# Opamps.net
KiCad netlist of a schematic drawn in Altium Designer
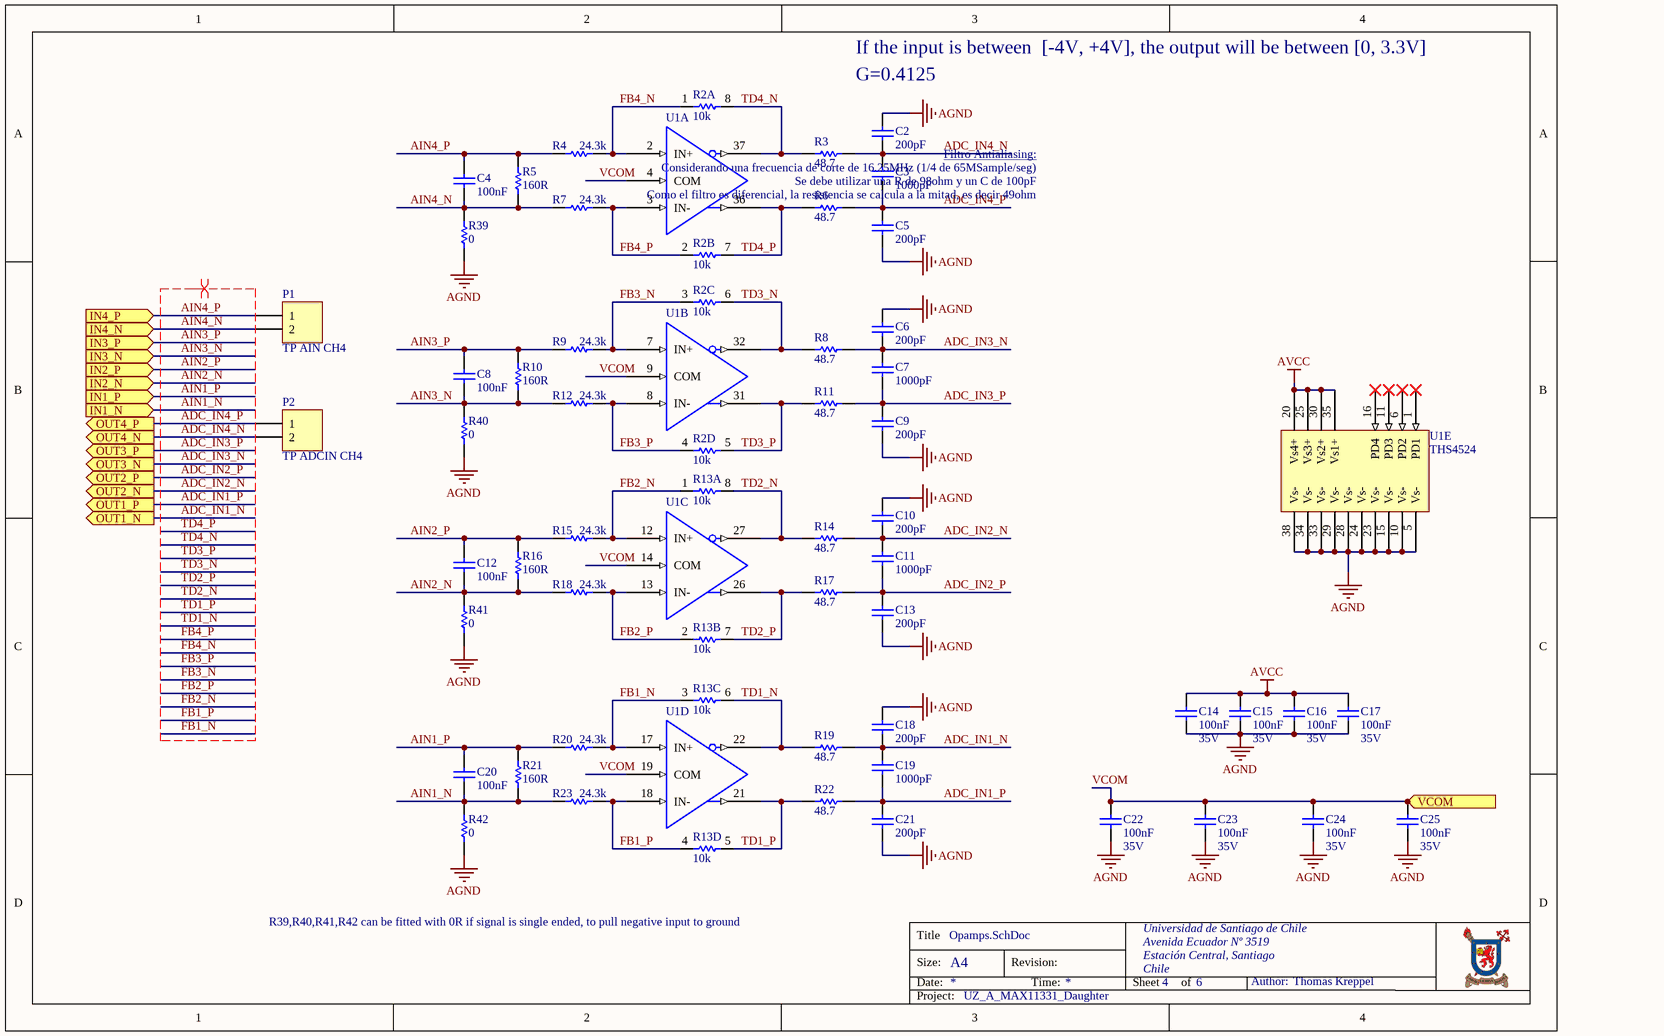
[diagram p0: Opamps.SchDoc]

(export (version "E")
  (design (tool "Eeschema 10.0.6"))
  (components
    (comp (ref "C2")
      (value "200pF")
      (footprint "CAP_0603")
      (description "Capacitor")
      (fields
        (field (name "MPN") "0603N201J500CT")
        (field (name "MF") "Walsin")
        (field (name "PUBLISHER") "Altium Limited")
      )
      (libsource (lib "Componentes_SOC") (part "Cap_0603"))
    )
    (comp (ref "C3")
      (value "1000pF")
      (footprint "CAP_0603")
      (description "Capacitor")
      (fields
        (field (name "MPN") "885012006029")
        (field (name "MF") "Würth Elektronik")
        (field (name "PUBLISHER") "Altium Limited")
      )
      (libsource (lib "Componentes_SOC") (part "Cap_0603"))
    )
    (comp (ref "C4")
      (value "100nF")
      (footprint "RES_1206")
      (description "Capacitor")
      (fields (field (name "MPN") "C1206C104K3RACTU") (field (name "VOLTAGE") "16V"))
      (libsource (lib "Componentes_SOC") (part "Cap_1206"))
    )
    (comp (ref "C5")
      (value "200pF")
      (footprint "CAP_0603")
      (description "Capacitor")
      (fields
        (field (name "MPN") "0603N201J500CT")
        (field (name "MF") "Walsin")
        (field (name "PUBLISHER") "Altium Limited")
      )
      (libsource (lib "Componentes_SOC") (part "Cap_0603"))
    )
    (comp (ref "C6")
      (value "200pF")
      (footprint "CAP_0603")
      (description "Capacitor")
      (fields
        (field (name "MPN") "0603N201J500CT")
        (field (name "MF") "Walsin")
        (field (name "PUBLISHER") "Altium Limited")
      )
      (libsource (lib "Componentes_SOC") (part "Cap_0603"))
    )
    (comp (ref "C7")
      (value "1000pF")
      (footprint "CAP_0603")
      (description "Capacitor")
      (fields
        (field (name "MPN") "885012006029")
        (field (name "MF") "Würth Elektronik")
        (field (name "PUBLISHER") "Altium Limited")
      )
      (libsource (lib "Componentes_SOC") (part "Cap_0603"))
    )
    (comp (ref "C8")
      (value "100nF")
      (footprint "RES_1206")
      (description "Capacitor")
      (fields (field (name "MPN") "C1206C104K3RACTU") (field (name "VOLTAGE") "16V"))
      (libsource (lib "Componentes_SOC") (part "Cap_1206"))
    )
    (comp (ref "C9")
      (value "200pF")
      (footprint "CAP_0603")
      (description "Capacitor")
      (fields
        (field (name "MPN") "0603N201J500CT")
        (field (name "MF") "Walsin")
        (field (name "PUBLISHER") "Altium Limited")
      )
      (libsource (lib "Componentes_SOC") (part "Cap_0603"))
    )
    (comp (ref "C10")
      (value "200pF")
      (footprint "CAP_0603")
      (description "Capacitor")
      (fields
        (field (name "MPN") "0603N201J500CT")
        (field (name "MF") "Walsin")
        (field (name "PUBLISHER") "Altium Limited")
      )
      (libsource (lib "Componentes_SOC") (part "Cap_0603"))
    )
    (comp (ref "C11")
      (value "1000pF")
      (footprint "CAP_0603")
      (description "Capacitor")
      (fields
        (field (name "MPN") "885012006029")
        (field (name "MF") "Würth Elektronik")
        (field (name "PUBLISHER") "Altium Limited")
      )
      (libsource (lib "Componentes_SOC") (part "Cap_0603"))
    )
    (comp (ref "C12")
      (value "100nF")
      (footprint "RES_1206")
      (description "Capacitor")
      (fields (field (name "MPN") "C1206C104K3RACTU") (field (name "VOLTAGE") "16V"))
      (libsource (lib "Componentes_SOC") (part "Cap_1206"))
    )
    (comp (ref "C13")
      (value "200pF")
      (footprint "CAP_0603")
      (description "Capacitor")
      (fields
        (field (name "MPN") "0603N201J500CT")
        (field (name "MF") "Walsin")
        (field (name "PUBLISHER") "Altium Limited")
      )
      (libsource (lib "Componentes_SOC") (part "Cap_0603"))
    )
    (comp (ref "C14")
      (value "100nF")
      (footprint "CAP_0603")
      (description "Capacitor")
      (fields
        (field (name "MPN") "C0603C104M5RACTU")
        (field (name "MF") "KEMET")
        (field (name "VOLTAGE") "35V")
        (field (name "PUBLISHER") "Altium Limited")
      )
      (libsource (lib "Componentes_SOC") (part "Cap_0603"))
    )
    (comp (ref "C15")
      (value "100nF")
      (footprint "CAP_0603")
      (description "Capacitor")
      (fields
        (field (name "MPN") "C0603C104M5RACTU")
        (field (name "MF") "KEMET")
        (field (name "VOLTAGE") "35V")
        (field (name "PUBLISHER") "Altium Limited")
      )
      (libsource (lib "Componentes_SOC") (part "Cap_0603"))
    )
    (comp (ref "C16")
      (value "100nF")
      (footprint "CAP_0603")
      (description "Capacitor")
      (fields
        (field (name "MPN") "C0603C104M5RACTU")
        (field (name "MF") "KEMET")
        (field (name "VOLTAGE") "35V")
        (field (name "PUBLISHER") "Altium Limited")
      )
      (libsource (lib "Componentes_SOC") (part "Cap_0603"))
    )
    (comp (ref "C17")
      (value "100nF")
      (footprint "CAP_0603")
      (description "Capacitor")
      (fields
        (field (name "MPN") "C0603C104M5RACTU")
        (field (name "MF") "KEMET")
        (field (name "VOLTAGE") "35V")
        (field (name "PUBLISHER") "Altium Limited")
      )
      (libsource (lib "Componentes_SOC") (part "Cap_0603"))
    )
    (comp (ref "C18")
      (value "200pF")
      (footprint "CAP_0603")
      (description "Capacitor")
      (fields
        (field (name "MPN") "0603N201J500CT")
        (field (name "MF") "Walsin")
        (field (name "PUBLISHER") "Altium Limited")
      )
      (libsource (lib "Componentes_SOC") (part "Cap_0603"))
    )
    (comp (ref "C19")
      (value "1000pF")
      (footprint "CAP_0603")
      (description "Capacitor")
      (fields
        (field (name "MPN") "885012006029")
        (field (name "MF") "Würth Elektronik")
        (field (name "PUBLISHER") "Altium Limited")
      )
      (libsource (lib "Componentes_SOC") (part "Cap_0603"))
    )
    (comp (ref "C20")
      (value "100nF")
      (footprint "RES_1206")
      (description "Capacitor")
      (fields (field (name "MPN") "C1206C104K3RACTU") (field (name "VOLTAGE") "16V"))
      (libsource (lib "Componentes_SOC") (part "Cap_1206"))
    )
    (comp (ref "C21")
      (value "200pF")
      (footprint "CAP_0603")
      (description "Capacitor")
      (fields
        (field (name "MPN") "0603N201J500CT")
        (field (name "MF") "Walsin")
        (field (name "PUBLISHER") "Altium Limited")
      )
      (libsource (lib "Componentes_SOC") (part "Cap_0603"))
    )
    (comp (ref "C22")
      (value "100nF")
      (footprint "CAP_0603")
      (description "Capacitor")
      (fields
        (field (name "MPN") "C0603C104M5RACTU")
        (field (name "MF") "KEMET")
        (field (name "VOLTAGE") "35V")
        (field (name "PUBLISHER") "Altium Limited")
      )
      (libsource (lib "Componentes_SOC") (part "Cap_0603"))
    )
    (comp (ref "C23")
      (value "100nF")
      (footprint "CAP_0603")
      (description "Capacitor")
      (fields
        (field (name "MPN") "C0603C104M5RACTU")
        (field (name "MF") "KEMET")
        (field (name "VOLTAGE") "35V")
        (field (name "PUBLISHER") "Altium Limited")
      )
      (libsource (lib "Componentes_SOC") (part "Cap_0603"))
    )
    (comp (ref "C24")
      (value "100nF")
      (footprint "CAP_0603")
      (description "Capacitor")
      (fields
        (field (name "MPN") "C0603C104M5RACTU")
        (field (name "MF") "KEMET")
        (field (name "VOLTAGE") "35V")
        (field (name "PUBLISHER") "Altium Limited")
      )
      (libsource (lib "Componentes_SOC") (part "Cap_0603"))
    )
    (comp (ref "C25")
      (value "100nF")
      (footprint "CAP_0603")
      (description "Capacitor")
      (fields
        (field (name "MPN") "C0603C104M5RACTU")
        (field (name "MF") "KEMET")
        (field (name "VOLTAGE") "35V")
        (field (name "PUBLISHER") "Altium Limited")
      )
      (libsource (lib "Componentes_SOC") (part "Cap_0603"))
    )
    (comp (ref "P1")
      (value "TP AIN CH4")
      (footprint "HDR1X2")
      (description "Header, 2-Pin")
      (fields (field (name "PUBLISHER") "Altium Limited"))
      (libsource (lib "Miscellaneous Connectors") (part "Header 2"))
    )
    (comp (ref "P2")
      (value "TP ADCIN CH4")
      (footprint "HDR1X2")
      (description "Header, 2-Pin")
      (fields (field (name "PUBLISHER") "Altium Limited"))
      (libsource (lib "Miscellaneous Connectors") (part "Header 2"))
    )
    (comp (ref "R2")
      (value "10k")
      (footprint "CAC-80P320X160-8N")
      (description "Chip Resistor Array 0606, 4xR")
      (fields
        (field (name "MF") "Vishay")
        (field (name "MPN") "ACASA1002S1002P100")
        (field (name "CREATED") "Kreppel_0420")
      )
      (libsource (lib "Componentes_SOC") (part "ResArray 1206"))
    )
    (comp (ref "R3")
      (value "48.7")
      (footprint "RES_0603")
      (fields
        (field (name "MPN") "ERA-3AEB48R7V")
        (field (name "MF") "Panasonic")
        (field (name "TOLERANCE") "0.1%")
        (field (name "PUBLISHER") "Altium Limited")
      )
      (libsource (lib "Componentes_SOC") (part "Res0603"))
    )
    (comp (ref "R4")
      (value "24.3k")
      (footprint "RES_0603")
      (fields
        (field (name "MPN") "ERJ-PB3B2432V")
        (field (name "MF") "Panasonic")
        (field (name "TOLERANCE") "0.1%")
        (field (name "PUBLISHER") "Altium Limited")
      )
      (libsource (lib "Componentes_SOC") (part "Res0603"))
    )
    (comp (ref "R5")
      (value "160R")
      (footprint "RES_1206")
      (description "Limiter Resistor")
      (fields
        (field (name "MPN") "RT1206BRD07160RL")
        (field (name "MF") "Yageo")
        (field (name "PUBLISHER") "Altium Limited")
      )
      (libsource (lib "Miscellaneous Devices") (part "Res Semi"))
    )
    (comp (ref "R6")
      (value "48.7")
      (footprint "RES_0603")
      (fields
        (field (name "MPN") "ERA-3AEB48R7V")
        (field (name "MF") "Panasonic")
        (field (name "TOLERANCE") "0.1%")
        (field (name "PUBLISHER") "Altium Limited")
      )
      (libsource (lib "Componentes_SOC") (part "Res0603"))
    )
    (comp (ref "R7")
      (value "24.3k")
      (footprint "RES_0603")
      (fields
        (field (name "MPN") "ERJ-PB3B2432V")
        (field (name "MF") "Panasonic")
        (field (name "TOLERANCE") "0.1%")
        (field (name "PUBLISHER") "Altium Limited")
      )
      (libsource (lib "Componentes_SOC") (part "Res0603"))
    )
    (comp (ref "R8")
      (value "48.7")
      (footprint "RES_0603")
      (fields
        (field (name "MPN") "ERA-3AEB48R7V")
        (field (name "MF") "Panasonic")
        (field (name "TOLERANCE") "0.1%")
        (field (name "PUBLISHER") "Altium Limited")
      )
      (libsource (lib "Componentes_SOC") (part "Res0603"))
    )
    (comp (ref "R9")
      (value "24.3k")
      (footprint "RES_0603")
      (fields
        (field (name "MPN") "ERJ-PB3B2432V")
        (field (name "MF") "Panasonic")
        (field (name "TOLERANCE") "0.1%")
        (field (name "PUBLISHER") "Altium Limited")
      )
      (libsource (lib "Componentes_SOC") (part "Res0603"))
    )
    (comp (ref "R10")
      (value "160R")
      (footprint "RES_1206")
      (description "Limiter Resistor")
      (fields
        (field (name "MPN") "RT1206BRD07160RL")
        (field (name "MF") "Yageo")
        (field (name "PUBLISHER") "Altium Limited")
      )
      (libsource (lib "Miscellaneous Devices") (part "Res Semi"))
    )
    (comp (ref "R11")
      (value "48.7")
      (footprint "RES_0603")
      (fields
        (field (name "MPN") "ERA-3AEB48R7V")
        (field (name "MF") "Panasonic")
        (field (name "TOLERANCE") "0.1%")
        (field (name "PUBLISHER") "Altium Limited")
      )
      (libsource (lib "Componentes_SOC") (part "Res0603"))
    )
    (comp (ref "R12")
      (value "24.3k")
      (footprint "RES_0603")
      (fields
        (field (name "MPN") "ERJ-PB3B2432V")
        (field (name "MF") "Panasonic")
        (field (name "TOLERANCE") "0.1%")
        (field (name "PUBLISHER") "Altium Limited")
      )
      (libsource (lib "Componentes_SOC") (part "Res0603"))
    )
    (comp (ref "R13")
      (value "10k")
      (footprint "CAC-80P320X160-8N")
      (description "Chip Resistor Array 0606, 4xR")
      (fields
        (field (name "MF") "Vishay")
        (field (name "MPN") "ACASA1002S1002P100")
        (field (name "CREATED") "Kreppel_0420")
      )
      (libsource (lib "Componentes_SOC") (part "ResArray 1206"))
    )
    (comp (ref "R14")
      (value "48.7")
      (footprint "RES_0603")
      (fields
        (field (name "MPN") "ERA-3AEB48R7V")
        (field (name "MF") "Panasonic")
        (field (name "TOLERANCE") "0.1%")
        (field (name "PUBLISHER") "Altium Limited")
      )
      (libsource (lib "Componentes_SOC") (part "Res0603"))
    )
    (comp (ref "R15")
      (value "24.3k")
      (footprint "RES_0603")
      (fields
        (field (name "MPN") "ERJ-PB3B2432V")
        (field (name "MF") "Panasonic")
        (field (name "TOLERANCE") "0.1%")
        (field (name "PUBLISHER") "Altium Limited")
      )
      (libsource (lib "Componentes_SOC") (part "Res0603"))
    )
    (comp (ref "R16")
      (value "160R")
      (footprint "RES_1206")
      (description "Limiter Resistor")
      (fields
        (field (name "MPN") "RT1206BRD07160RL")
        (field (name "MF") "Yageo")
        (field (name "PUBLISHER") "Altium Limited")
      )
      (libsource (lib "Miscellaneous Devices") (part "Res Semi"))
    )
    (comp (ref "R17")
      (value "48.7")
      (footprint "RES_0603")
      (fields
        (field (name "MPN") "ERA-3AEB48R7V")
        (field (name "MF") "Panasonic")
        (field (name "TOLERANCE") "0.1%")
        (field (name "PUBLISHER") "Altium Limited")
      )
      (libsource (lib "Componentes_SOC") (part "Res0603"))
    )
    (comp (ref "R18")
      (value "24.3k")
      (footprint "RES_0603")
      (fields
        (field (name "MPN") "ERJ-PB3B2432V")
        (field (name "MF") "Panasonic")
        (field (name "TOLERANCE") "0.1%")
        (field (name "PUBLISHER") "Altium Limited")
      )
      (libsource (lib "Componentes_SOC") (part "Res0603"))
    )
    (comp (ref "R19")
      (value "48.7")
      (footprint "RES_0603")
      (fields
        (field (name "MPN") "ERA-3AEB48R7V")
        (field (name "MF") "Panasonic")
        (field (name "TOLERANCE") "0.1%")
        (field (name "PUBLISHER") "Altium Limited")
      )
      (libsource (lib "Componentes_SOC") (part "Res0603"))
    )
    (comp (ref "R20")
      (value "24.3k")
      (footprint "RES_0603")
      (fields
        (field (name "MPN") "ERJ-PB3B2432V")
        (field (name "MF") "Panasonic")
        (field (name "TOLERANCE") "0.1%")
        (field (name "PUBLISHER") "Altium Limited")
      )
      (libsource (lib "Componentes_SOC") (part "Res0603"))
    )
    (comp (ref "R21")
      (value "160R")
      (footprint "RES_1206")
      (description "Limiter Resistor")
      (fields
        (field (name "MPN") "RT1206BRD07160RL")
        (field (name "MF") "Yageo")
        (field (name "PUBLISHER") "Altium Limited")
      )
      (libsource (lib "Miscellaneous Devices") (part "Res Semi"))
    )
    (comp (ref "R22")
      (value "48.7")
      (footprint "RES_0603")
      (fields
        (field (name "MPN") "ERA-3AEB48R7V")
        (field (name "MF") "Panasonic")
        (field (name "TOLERANCE") "0.1%")
        (field (name "PUBLISHER") "Altium Limited")
      )
      (libsource (lib "Componentes_SOC") (part "Res0603"))
    )
    (comp (ref "R23")
      (value "24.3k")
      (footprint "RES_0603")
      (fields
        (field (name "MPN") "ERJ-PB3B2432V")
        (field (name "MF") "Panasonic")
        (field (name "TOLERANCE") "0.1%")
        (field (name "PUBLISHER") "Altium Limited")
      )
      (libsource (lib "Componentes_SOC") (part "Res0603"))
    )
    (comp (ref "R39")
      (value "0")
      (footprint "RES_0603")
      (fields
        (field (name "MPN") "RC0603JR-070RL")
        (field (name "MF") "Yageo")
        (field (name "TOLERANCE") "1%")
        (field (name "PUBLISHER") "Altium Limited")
      )
      (libsource (lib "Componentes_SOC") (part "Res0603"))
    )
    (comp (ref "R40")
      (value "0")
      (footprint "RES_0603")
      (fields
        (field (name "MPN") "RC0603JR-070RL")
        (field (name "MF") "Yageo")
        (field (name "TOLERANCE") "1%")
        (field (name "PUBLISHER") "Altium Limited")
      )
      (libsource (lib "Componentes_SOC") (part "Res0603"))
    )
    (comp (ref "R41")
      (value "0")
      (footprint "RES_0603")
      (fields
        (field (name "MPN") "RC0603JR-070RL")
        (field (name "MF") "Yageo")
        (field (name "TOLERANCE") "1%")
        (field (name "PUBLISHER") "Altium Limited")
      )
      (libsource (lib "Componentes_SOC") (part "Res0603"))
    )
    (comp (ref "R42")
      (value "0")
      (footprint "RES_0603")
      (fields
        (field (name "MPN") "RC0603JR-070RL")
        (field (name "MF") "Yageo")
        (field (name "TOLERANCE") "1%")
        (field (name "PUBLISHER") "Altium Limited")
      )
      (libsource (lib "Componentes_SOC") (part "Res0603"))
    )
    (comp (ref "U1")
      (value "THS4524")
      (footprint "THS4524 Footprint")
      (description "Quad Channel fully differential Amplilfier")
      (fields
        (field (name "MF") "Texas Instruments")
        (field (name "LCSC PART NUMBER") "C2057434")
        (field (name "CREATED") "20190720_Kreppel")
      )
      (libsource (lib "Componentes_SOC") (part "THS4524_1"))
    )
  )
  (nets
    (net (code "1") (name "/ADC_IN1_N") (class "Default")
      (node (ref "C18") (pin "2") (pinfunction "2_2") (pintype "passive"))
      (node (ref "C19") (pin "1") (pinfunction "1_1") (pintype "passive"))
      (node (ref "R19") (pin "1") (pinfunction "1_1") (pintype "passive"))
    )
    (net (code "2") (name "/ADC_IN1_P") (class "Default")
      (node (ref "C19") (pin "2") (pinfunction "2_2") (pintype "passive"))
      (node (ref "C21") (pin "1") (pinfunction "1_1") (pintype "passive"))
      (node (ref "R22") (pin "1") (pinfunction "1_1") (pintype "passive"))
    )
    (net (code "3") (name "/ADC_IN2_N") (class "Default")
      (node (ref "C10") (pin "2") (pinfunction "2_2") (pintype "passive"))
      (node (ref "C11") (pin "1") (pinfunction "1_1") (pintype "passive"))
      (node (ref "R14") (pin "1") (pinfunction "1_1") (pintype "passive"))
    )
    (net (code "4") (name "/ADC_IN2_P") (class "Default")
      (node (ref "C11") (pin "2") (pinfunction "2_2") (pintype "passive"))
      (node (ref "C13") (pin "1") (pinfunction "1_1") (pintype "passive"))
      (node (ref "R17") (pin "1") (pinfunction "1_1") (pintype "passive"))
    )
    (net (code "5") (name "/ADC_IN3_N") (class "Default")
      (node (ref "C6") (pin "2") (pinfunction "2_2") (pintype "passive"))
      (node (ref "C7") (pin "1") (pinfunction "1_1") (pintype "passive"))
      (node (ref "R8") (pin "1") (pinfunction "1_1") (pintype "passive"))
    )
    (net (code "6") (name "/ADC_IN3_P") (class "Default")
      (node (ref "C7") (pin "2") (pinfunction "2_2") (pintype "passive"))
      (node (ref "C9") (pin "1") (pinfunction "1_1") (pintype "passive"))
      (node (ref "R11") (pin "1") (pinfunction "1_1") (pintype "passive"))
    )
    (net (code "7") (name "/ADC_IN4_N") (class "Default")
      (node (ref "C2") (pin "2") (pinfunction "2_2") (pintype "passive"))
      (node (ref "C3") (pin "1") (pinfunction "1_1") (pintype "passive"))
      (node (ref "P2") (pin "2") (pinfunction "2_2") (pintype "passive"))
      (node (ref "R3") (pin "1") (pinfunction "1_1") (pintype "passive"))
    )
    (net (code "8") (name "/ADC_IN4_P") (class "Default")
      (node (ref "C3") (pin "2") (pinfunction "2_2") (pintype "passive"))
      (node (ref "C5") (pin "1") (pinfunction "1_1") (pintype "passive"))
      (node (ref "P2") (pin "1") (pinfunction "1_1") (pintype "passive"))
      (node (ref "R6") (pin "1") (pinfunction "1_1") (pintype "passive"))
    )
    (net (code "9") (name "/AIN1_N") (class "Default")
      (node (ref "C20") (pin "2") (pinfunction "2_2") (pintype "passive"))
      (node (ref "R21") (pin "2") (pinfunction "2_2") (pintype "passive"))
      (node (ref "R23") (pin "2") (pinfunction "2_2") (pintype "passive"))
      (node (ref "R42") (pin "1") (pinfunction "1_1") (pintype "passive"))
    )
    (net (code "10") (name "/AIN1_P") (class "Default")
      (node (ref "C20") (pin "1") (pinfunction "1_1") (pintype "passive"))
      (node (ref "R20") (pin "2") (pinfunction "2_2") (pintype "passive"))
      (node (ref "R21") (pin "1") (pinfunction "1_1") (pintype "passive"))
    )
    (net (code "11") (name "/AIN2_N") (class "Default")
      (node (ref "C12") (pin "2") (pinfunction "2_2") (pintype "passive"))
      (node (ref "R16") (pin "2") (pinfunction "2_2") (pintype "passive"))
      (node (ref "R18") (pin "2") (pinfunction "2_2") (pintype "passive"))
      (node (ref "R41") (pin "1") (pinfunction "1_1") (pintype "passive"))
    )
    (net (code "12") (name "/AIN2_P") (class "Default")
      (node (ref "C12") (pin "1") (pinfunction "1_1") (pintype "passive"))
      (node (ref "R15") (pin "2") (pinfunction "2_2") (pintype "passive"))
      (node (ref "R16") (pin "1") (pinfunction "1_1") (pintype "passive"))
    )
    (net (code "13") (name "/AIN3_N") (class "Default")
      (node (ref "C8") (pin "2") (pinfunction "2_2") (pintype "passive"))
      (node (ref "R10") (pin "2") (pinfunction "2_2") (pintype "passive"))
      (node (ref "R12") (pin "2") (pinfunction "2_2") (pintype "passive"))
      (node (ref "R40") (pin "1") (pinfunction "1_1") (pintype "passive"))
    )
    (net (code "14") (name "/AIN3_P") (class "Default")
      (node (ref "C8") (pin "1") (pinfunction "1_1") (pintype "passive"))
      (node (ref "R10") (pin "1") (pinfunction "1_1") (pintype "passive"))
      (node (ref "R9") (pin "2") (pinfunction "2_2") (pintype "passive"))
    )
    (net (code "15") (name "/AIN4_N") (class "Default")
      (node (ref "C4") (pin "2") (pinfunction "2_2") (pintype "passive"))
      (node (ref "P1") (pin "2") (pinfunction "2_2") (pintype "passive"))
      (node (ref "R39") (pin "1") (pinfunction "1_1") (pintype "passive"))
      (node (ref "R5") (pin "2") (pinfunction "2_2") (pintype "passive"))
      (node (ref "R7") (pin "2") (pinfunction "2_2") (pintype "passive"))
    )
    (net (code "16") (name "/AIN4_P") (class "Default")
      (node (ref "C4") (pin "1") (pinfunction "1_1") (pintype "passive"))
      (node (ref "P1") (pin "1") (pinfunction "1_1") (pintype "passive"))
      (node (ref "R4") (pin "2") (pinfunction "2_2") (pintype "passive"))
      (node (ref "R5") (pin "1") (pinfunction "1_1") (pintype "passive"))
    )
    (net (code "17") (name "/FB1_N") (class "Default")
      (node (ref "R13") (pin "3") (pinfunction "1_3") (pintype "passive"))
      (node (ref "R20") (pin "1") (pinfunction "1_1") (pintype "passive"))
      (node (ref "U1") (pin "17") (pinfunction "IN+_17") (pintype "input"))
    )
    (net (code "18") (name "/FB1_P") (class "Default")
      (node (ref "R13") (pin "4") (pinfunction "1_4") (pintype "passive"))
      (node (ref "R23") (pin "1") (pinfunction "1_1") (pintype "passive"))
      (node (ref "U1") (pin "18") (pinfunction "IN-_18") (pintype "input"))
    )
    (net (code "19") (name "/FB2_N") (class "Default")
      (node (ref "R13") (pin "1") (pinfunction "1_1") (pintype "passive"))
      (node (ref "R15") (pin "1") (pinfunction "1_1") (pintype "passive"))
      (node (ref "U1") (pin "12") (pinfunction "IN+_12") (pintype "input"))
    )
    (net (code "20") (name "/FB2_P") (class "Default")
      (node (ref "R13") (pin "2") (pinfunction "1_2") (pintype "passive"))
      (node (ref "R18") (pin "1") (pinfunction "1_1") (pintype "passive"))
      (node (ref "U1") (pin "13") (pinfunction "IN-_13") (pintype "input"))
    )
    (net (code "21") (name "/FB3_N") (class "Default")
      (node (ref "R2") (pin "3") (pinfunction "1_3") (pintype "passive"))
      (node (ref "R9") (pin "1") (pinfunction "1_1") (pintype "passive"))
      (node (ref "U1") (pin "7") (pinfunction "IN+_7") (pintype "input"))
    )
    (net (code "22") (name "/FB3_P") (class "Default")
      (node (ref "R12") (pin "1") (pinfunction "1_1") (pintype "passive"))
      (node (ref "R2") (pin "4") (pinfunction "1_4") (pintype "passive"))
      (node (ref "U1") (pin "8") (pinfunction "IN-_8") (pintype "input"))
    )
    (net (code "23") (name "/FB4_N") (class "Default")
      (node (ref "R2") (pin "1") (pinfunction "1_1") (pintype "passive"))
      (node (ref "R4") (pin "1") (pinfunction "1_1") (pintype "passive"))
      (node (ref "U1") (pin "2") (pinfunction "IN+_2") (pintype "input"))
    )
    (net (code "24") (name "/FB4_P") (class "Default")
      (node (ref "R2") (pin "2") (pinfunction "1_2") (pintype "passive"))
      (node (ref "R7") (pin "1") (pinfunction "1_1") (pintype "passive"))
      (node (ref "U1") (pin "3") (pinfunction "IN-_3") (pintype "input"))
    )
    (net (code "25") (name "/TD1_N") (class "Default")
      (node (ref "R13") (pin "6") (pinfunction "2_6") (pintype "passive"))
      (node (ref "R19") (pin "2") (pinfunction "2_2") (pintype "passive"))
      (node (ref "U1") (pin "22") (pinfunction "OUT-_22") (pintype "output"))
    )
    (net (code "26") (name "/TD1_P") (class "Default")
      (node (ref "R13") (pin "5") (pinfunction "2_5") (pintype "passive"))
      (node (ref "R22") (pin "2") (pinfunction "2_2") (pintype "passive"))
      (node (ref "U1") (pin "21") (pinfunction "OUT+_21") (pintype "output"))
    )
    (net (code "27") (name "/TD2_N") (class "Default")
      (node (ref "R13") (pin "8") (pinfunction "2_8") (pintype "passive"))
      (node (ref "R14") (pin "2") (pinfunction "2_2") (pintype "passive"))
      (node (ref "U1") (pin "27") (pinfunction "OUT-_27") (pintype "output"))
    )
    (net (code "28") (name "/TD2_P") (class "Default")
      (node (ref "R13") (pin "7") (pinfunction "2_7") (pintype "passive"))
      (node (ref "R17") (pin "2") (pinfunction "2_2") (pintype "passive"))
      (node (ref "U1") (pin "26") (pinfunction "OUT+_26") (pintype "output"))
    )
    (net (code "29") (name "/TD3_N") (class "Default")
      (node (ref "R2") (pin "6") (pinfunction "2_6") (pintype "passive"))
      (node (ref "R8") (pin "2") (pinfunction "2_2") (pintype "passive"))
      (node (ref "U1") (pin "32") (pinfunction "OUT-_32") (pintype "output"))
    )
    (net (code "30") (name "/TD3_P") (class "Default")
      (node (ref "R11") (pin "2") (pinfunction "2_2") (pintype "passive"))
      (node (ref "R2") (pin "5") (pinfunction "2_5") (pintype "passive"))
      (node (ref "U1") (pin "31") (pinfunction "OUT+_31") (pintype "output"))
    )
    (net (code "31") (name "/TD4_N") (class "Default")
      (node (ref "R2") (pin "8") (pinfunction "2_8") (pintype "passive"))
      (node (ref "R3") (pin "2") (pinfunction "2_2") (pintype "passive"))
      (node (ref "U1") (pin "37") (pinfunction "OUT-_37") (pintype "output"))
    )
    (net (code "32") (name "/TD4_P") (class "Default")
      (node (ref "R2") (pin "7") (pinfunction "2_7") (pintype "passive"))
      (node (ref "R6") (pin "2") (pinfunction "2_2") (pintype "passive"))
      (node (ref "U1") (pin "36") (pinfunction "OUT+_36") (pintype "output"))
    )
    (net (code "33") (name "/VCOM") (class "Default")
      (node (ref "C22") (pin "2") (pinfunction "2_2") (pintype "passive"))
      (node (ref "C23") (pin "2") (pinfunction "2_2") (pintype "passive"))
      (node (ref "C24") (pin "2") (pinfunction "2_2") (pintype "passive"))
      (node (ref "C25") (pin "2") (pinfunction "2_2") (pintype "passive"))
      (node (ref "U1") (pin "14") (pinfunction "COM_14") (pintype "input"))
      (node (ref "U1") (pin "19") (pinfunction "COM_19") (pintype "input"))
      (node (ref "U1") (pin "4") (pinfunction "COM_4") (pintype "input"))
      (node (ref "U1") (pin "9") (pinfunction "COM_9") (pintype "input"))
    )
    (net (code "34") (name "AGND") (class "Default")
      (node (ref "C10") (pin "1") (pinfunction "1_1") (pintype "passive"))
      (node (ref "C13") (pin "2") (pinfunction "2_2") (pintype "passive"))
      (node (ref "C14") (pin "2") (pinfunction "2_2") (pintype "passive"))
      (node (ref "C15") (pin "2") (pinfunction "2_2") (pintype "passive"))
      (node (ref "C16") (pin "2") (pinfunction "2_2") (pintype "passive"))
      (node (ref "C17") (pin "2") (pinfunction "2_2") (pintype "passive"))
      (node (ref "C18") (pin "1") (pinfunction "1_1") (pintype "passive"))
      (node (ref "C2") (pin "1") (pinfunction "1_1") (pintype "passive"))
      (node (ref "C21") (pin "2") (pinfunction "2_2") (pintype "passive"))
      (node (ref "C22") (pin "1") (pinfunction "1_1") (pintype "passive"))
      (node (ref "C23") (pin "1") (pinfunction "1_1") (pintype "passive"))
      (node (ref "C24") (pin "1") (pinfunction "1_1") (pintype "passive"))
      (node (ref "C25") (pin "1") (pinfunction "1_1") (pintype "passive"))
      (node (ref "C5") (pin "2") (pinfunction "2_2") (pintype "passive"))
      (node (ref "C6") (pin "1") (pinfunction "1_1") (pintype "passive"))
      (node (ref "C9") (pin "2") (pinfunction "2_2") (pintype "passive"))
      (node (ref "R39") (pin "2") (pinfunction "2_2") (pintype "passive"))
      (node (ref "R40") (pin "2") (pinfunction "2_2") (pintype "passive"))
      (node (ref "R41") (pin "2") (pinfunction "2_2") (pintype "passive"))
      (node (ref "R42") (pin "2") (pinfunction "2_2") (pintype "passive"))
      (node (ref "U1") (pin "10") (pinfunction "Vs-_10") (pintype "power_in"))
      (node (ref "U1") (pin "15") (pinfunction "Vs-_15") (pintype "passive"))
      (node (ref "U1") (pin "23") (pinfunction "Vs-_23") (pintype "power_in"))
      (node (ref "U1") (pin "24") (pinfunction "Vs-_24") (pintype "power_in"))
      (node (ref "U1") (pin "28") (pinfunction "Vs-_28") (pintype "power_in"))
      (node (ref "U1") (pin "29") (pinfunction "Vs-_29") (pintype "power_in"))
      (node (ref "U1") (pin "33") (pinfunction "Vs-_33") (pintype "power_in"))
      (node (ref "U1") (pin "34") (pinfunction "Vs-_34") (pintype "power_in"))
      (node (ref "U1") (pin "38") (pinfunction "Vs-_38") (pintype "power_in"))
      (node (ref "U1") (pin "5") (pinfunction "Vs-_5") (pintype "power_in"))
    )
    (net (code "35") (name "AVCC") (class "Default")
      (node (ref "C14") (pin "1") (pinfunction "1_1") (pintype "passive"))
      (node (ref "C15") (pin "1") (pinfunction "1_1") (pintype "passive"))
      (node (ref "C16") (pin "1") (pinfunction "1_1") (pintype "passive"))
      (node (ref "C17") (pin "1") (pinfunction "1_1") (pintype "passive"))
      (node (ref "U1") (pin "20") (pinfunction "Vs4+_20") (pintype "power_in"))
      (node (ref "U1") (pin "25") (pinfunction "Vs3+_25") (pintype "power_in"))
      (node (ref "U1") (pin "30") (pinfunction "Vs2+_30") (pintype "power_in"))
      (node (ref "U1") (pin "35") (pinfunction "Vs1+_35") (pintype "power_in"))
    )
    (net (code "36") (name "unconnected-(U1E-PD1-Pad1)") (class "Default")
      (node (ref "U1") (pin "1") (pinfunction "PD1_1") (pintype "input+no_connect"))
    )
    (net (code "37") (name "unconnected-(U1E-PD2-Pad6)") (class "Default")
      (node (ref "U1") (pin "6") (pinfunction "PD2_6") (pintype "input+no_connect"))
    )
    (net (code "38") (name "unconnected-(U1E-PD3-Pad11)") (class "Default")
      (node (ref "U1") (pin "11") (pinfunction "PD3_11") (pintype "input+no_connect"))
    )
    (net (code "39") (name "unconnected-(U1E-PD4-Pad16)") (class "Default")
      (node (ref "U1") (pin "16") (pinfunction "PD4_16") (pintype "input+no_connect"))
    )
  )
)
